# rl_energy_board.net
KiCad netlist of a schematic drawn in EAGLE
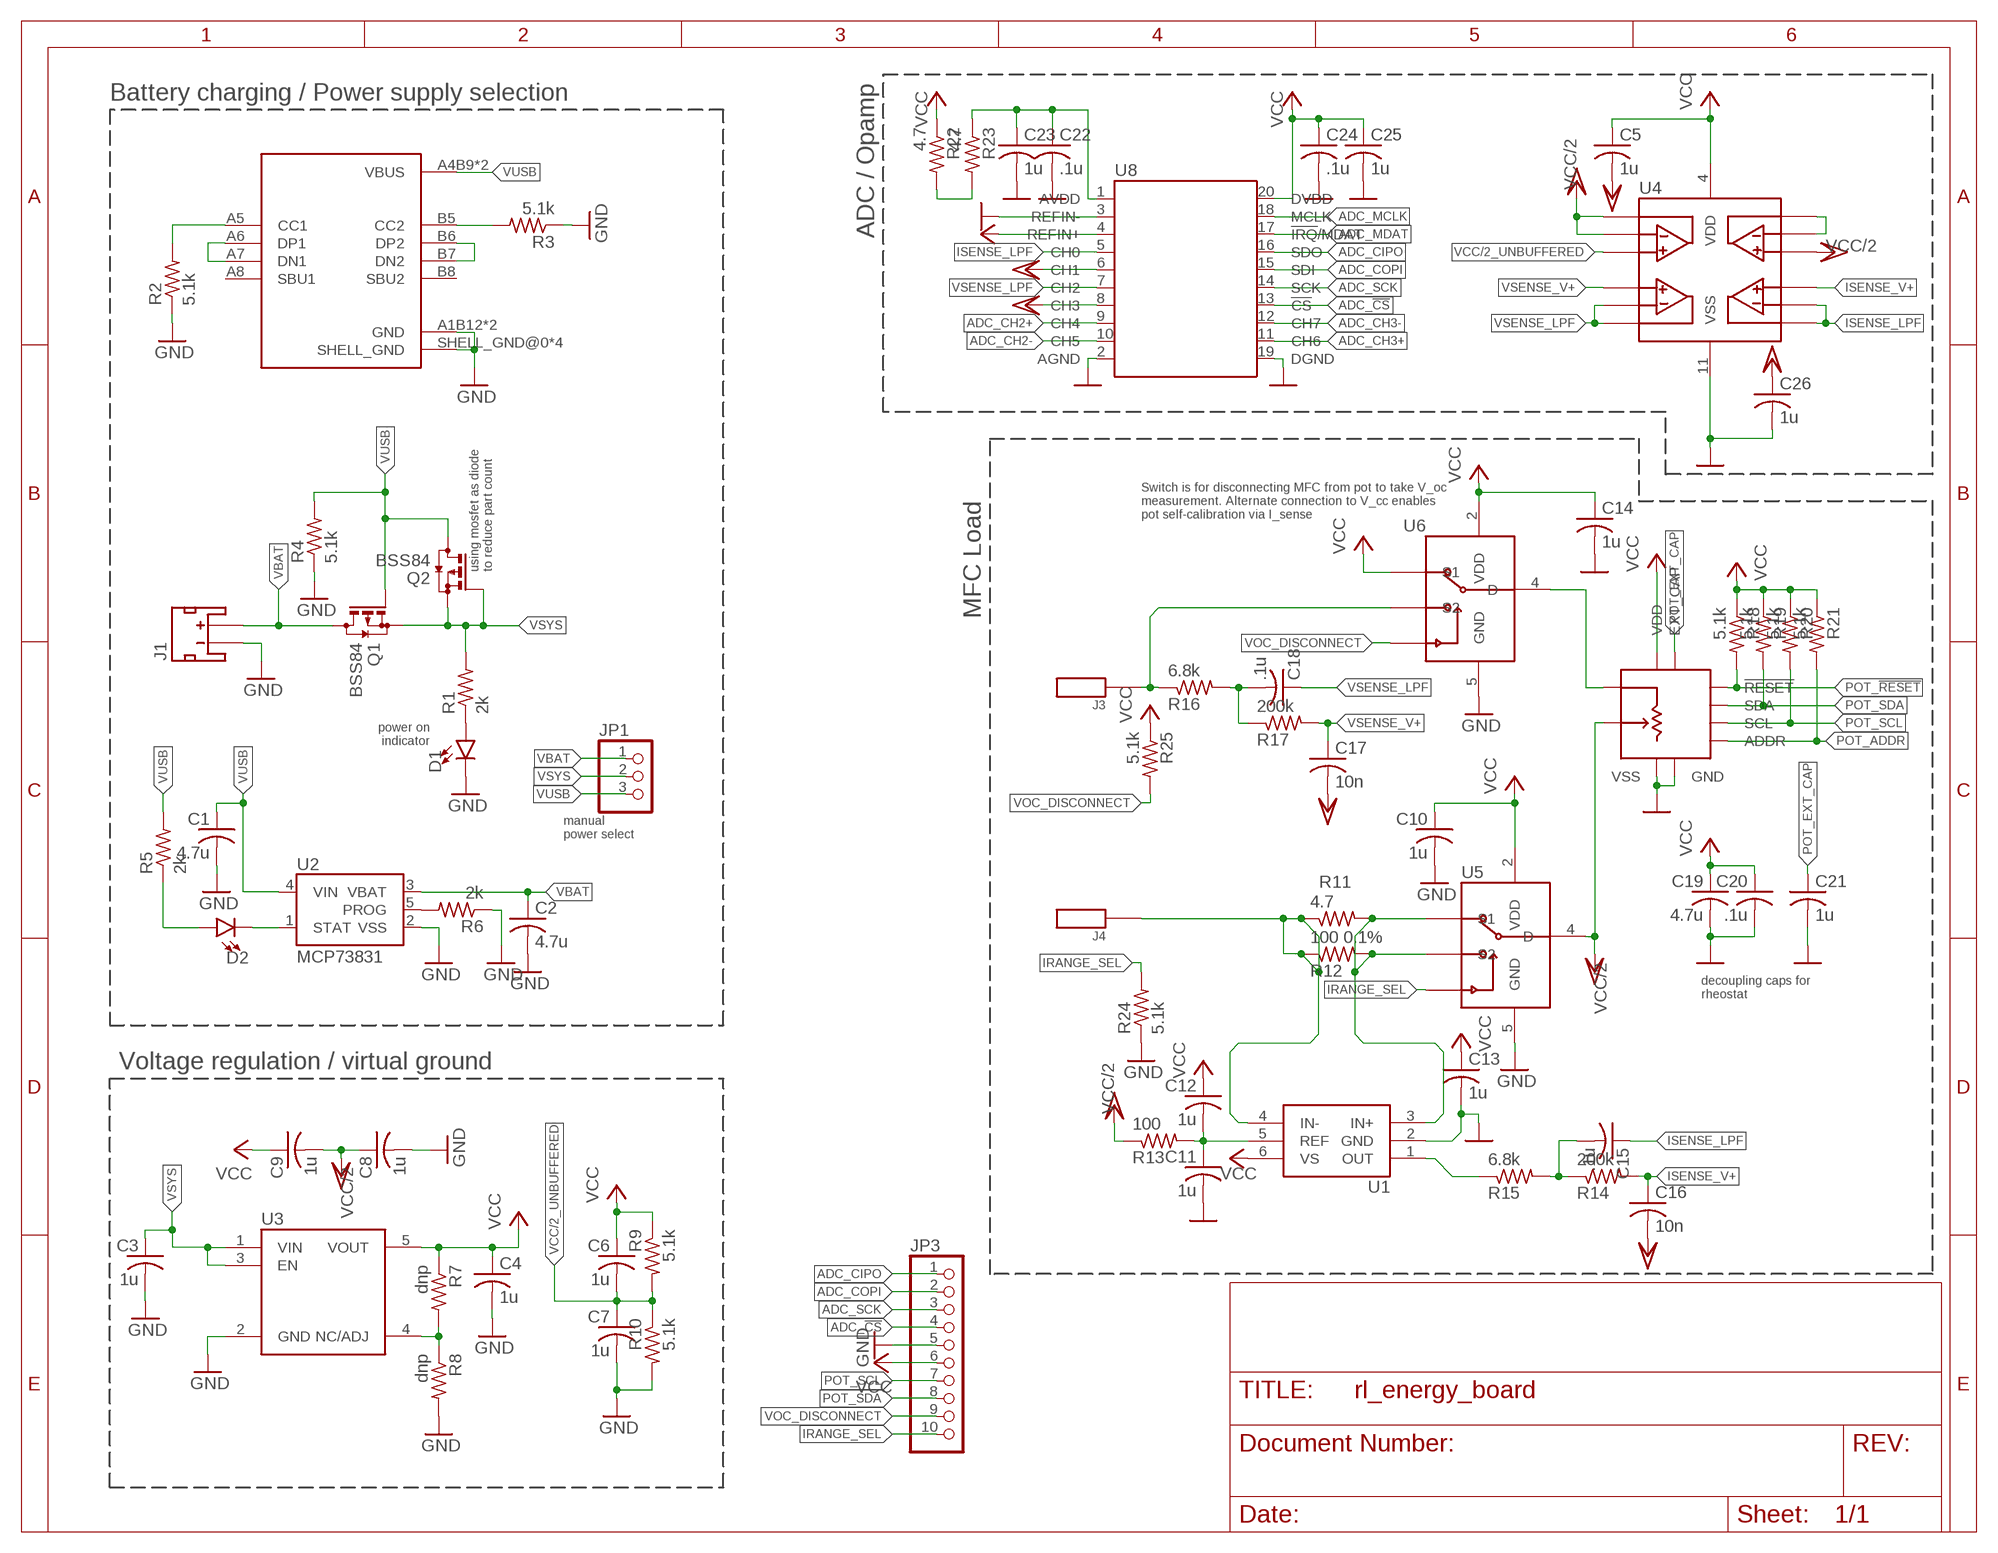
[diagram p0: schematic, sheet 1]

(export (version "E")
  (design (tool "Eeschema 10.0.6"))
  (components
    (comp (ref "C1")
      (value "4.7u")
      (footprint "eagle-import:C0603")
      (libsource (lib "eagle-import") (part "C-USC0603"))
    )
    (comp (ref "C2")
      (value "4.7u")
      (footprint "eagle-import:C0603")
      (libsource (lib "eagle-import") (part "C-USC0603"))
    )
    (comp (ref "C3")
      (value "1u")
      (footprint "eagle-import:C0603")
      (libsource (lib "eagle-import") (part "C-USC0603"))
    )
    (comp (ref "C4")
      (value "1u")
      (footprint "eagle-import:C0603")
      (libsource (lib "eagle-import") (part "C-USC0603"))
    )
    (comp (ref "C5")
      (value "1u")
      (footprint "eagle-import:C0603")
      (libsource (lib "eagle-import") (part "C-USC0603"))
    )
    (comp (ref "C6")
      (value "1u")
      (footprint "eagle-import:C0603")
      (libsource (lib "eagle-import") (part "C-USC0603"))
    )
    (comp (ref "C7")
      (value "1u")
      (footprint "eagle-import:C0603")
      (libsource (lib "eagle-import") (part "C-USC0603"))
    )
    (comp (ref "C8")
      (value "1u")
      (footprint "eagle-import:C0603")
      (libsource (lib "eagle-import") (part "C-USC0603"))
    )
    (comp (ref "C9")
      (value "1u")
      (footprint "eagle-import:C0603")
      (libsource (lib "eagle-import") (part "C-USC0603"))
    )
    (comp (ref "C10")
      (value "1u")
      (footprint "eagle-import:C0603")
      (libsource (lib "eagle-import") (part "C-USC0603"))
    )
    (comp (ref "C11")
      (value "1u")
      (footprint "eagle-import:C0603")
      (libsource (lib "eagle-import") (part "C-USC0603"))
    )
    (comp (ref "C12")
      (value "1u")
      (footprint "eagle-import:C0603")
      (libsource (lib "eagle-import") (part "C-USC0603"))
    )
    (comp (ref "C13")
      (value "1u")
      (footprint "eagle-import:C0603")
      (libsource (lib "eagle-import") (part "C-USC0603"))
    )
    (comp (ref "C14")
      (value "1u")
      (footprint "eagle-import:C0603")
      (libsource (lib "eagle-import") (part "C-USC0603"))
    )
    (comp (ref "C15")
      (value ".1u")
      (footprint "eagle-import:C0603")
      (libsource (lib "eagle-import") (part "C-USC0603"))
    )
    (comp (ref "C16")
      (value "10n")
      (footprint "eagle-import:C0603")
      (libsource (lib "eagle-import") (part "C-USC0603"))
    )
    (comp (ref "C17")
      (value "10n")
      (footprint "eagle-import:C0603")
      (libsource (lib "eagle-import") (part "C-USC0603"))
    )
    (comp (ref "C18")
      (value ".1u")
      (footprint "eagle-import:C0603")
      (libsource (lib "eagle-import") (part "C-USC0603"))
    )
    (comp (ref "C19")
      (value "4.7u")
      (footprint "eagle-import:C0603")
      (libsource (lib "eagle-import") (part "C-USC0603"))
    )
    (comp (ref "C20")
      (value ".1u")
      (footprint "eagle-import:C0603")
      (libsource (lib "eagle-import") (part "C-USC0603"))
    )
    (comp (ref "C21")
      (value "1u")
      (footprint "eagle-import:C0603")
      (libsource (lib "eagle-import") (part "C-USC0603"))
    )
    (comp (ref "C22")
      (value ".1u")
      (footprint "eagle-import:C0603")
      (libsource (lib "eagle-import") (part "C-USC0603"))
    )
    (comp (ref "C23")
      (value "1u")
      (footprint "eagle-import:C0603")
      (libsource (lib "eagle-import") (part "C-USC0603"))
    )
    (comp (ref "C24")
      (value ".1u")
      (footprint "eagle-import:C0603")
      (libsource (lib "eagle-import") (part "C-USC0603"))
    )
    (comp (ref "C25")
      (value "1u")
      (footprint "eagle-import:C0603")
      (libsource (lib "eagle-import") (part "C-USC0603"))
    )
    (comp (ref "C26")
      (value "1u")
      (footprint "eagle-import:C0603")
      (libsource (lib "eagle-import") (part "C-USC0603"))
    )
    (comp (ref "D1")
      (value "LED0603")
      (footprint "eagle-import:LED-0603")
      (fields (field (name "MFR") "Lite-On Inc."))
      (libsource (lib "eagle-import") (part "LED0603"))
    )
    (comp (ref "D2")
      (value "LED0603")
      (footprint "eagle-import:LED-0603")
      (fields (field (name "MFR") "Lite-On Inc."))
      (libsource (lib "eagle-import") (part "LED0603"))
    )
    (comp (ref "J1")
      (value "JST_2MM_MALE")
      (footprint "eagle-import:JST-2-SMD")
      (fields (field (name "MFR") "JST"))
      (libsource (lib "eagle-import") (part "JST_2MM_MALE"))
    )
    (comp (ref "J2")
      (value "USB4105")
      (footprint "eagle-import:USB4105")
      (libsource (lib "eagle-import") (part "USB4105"))
    )
    (comp (ref "J3")
      (value "CT3151V1-X")
      (footprint "eagle-import:CT3151V1")
      (libsource (lib "eagle-import") (part "CT3151V1-X"))
    )
    (comp (ref "J4")
      (value "CT3151V1-X")
      (footprint "eagle-import:CT3151V1")
      (libsource (lib "eagle-import") (part "CT3151V1-X"))
    )
    (comp (ref "JP1")
      (value "PINHD-1X3")
      (footprint "eagle-import:1X03")
      (libsource (lib "eagle-import") (part "PINHD-1X3"))
    )
    (comp (ref "JP3")
      (value "PINHD-1X10")
      (footprint "eagle-import:1X10")
      (libsource (lib "eagle-import") (part "PINHD-1X10"))
    )
    (comp (ref "Q1")
      (value "BSS84")
      (footprint "eagle-import:SOT23")
      (libsource (lib "eagle-import") (part "BSS84"))
    )
    (comp (ref "Q2")
      (value "BSS84")
      (footprint "eagle-import:SOT23")
      (libsource (lib "eagle-import") (part "BSS84"))
    )
    (comp (ref "R1")
      (value "2k")
      (footprint "eagle-import:R0603")
      (libsource (lib "eagle-import") (part "R-US_R0603"))
    )
    (comp (ref "R2")
      (value "5.1k")
      (footprint "eagle-import:R0603")
      (libsource (lib "eagle-import") (part "R-US_R0603"))
    )
    (comp (ref "R3")
      (value "5.1k")
      (footprint "eagle-import:R0603")
      (libsource (lib "eagle-import") (part "R-US_R0603"))
    )
    (comp (ref "R4")
      (value "5.1k")
      (footprint "eagle-import:R0603")
      (libsource (lib "eagle-import") (part "R-US_R0603"))
    )
    (comp (ref "R5")
      (value "2k")
      (footprint "eagle-import:R0603")
      (libsource (lib "eagle-import") (part "R-US_R0603"))
    )
    (comp (ref "R6")
      (value "2k")
      (footprint "eagle-import:R0603")
      (libsource (lib "eagle-import") (part "R-US_R0603"))
    )
    (comp (ref "R7")
      (value "dnp")
      (footprint "eagle-import:R0603")
      (libsource (lib "eagle-import") (part "R-US_R0603"))
    )
    (comp (ref "R8")
      (value "dnp")
      (footprint "eagle-import:R0603")
      (libsource (lib "eagle-import") (part "R-US_R0603"))
    )
    (comp (ref "R9")
      (value "5.1k")
      (footprint "eagle-import:R0603")
      (libsource (lib "eagle-import") (part "R-US_R0603"))
    )
    (comp (ref "R10")
      (value "5.1k")
      (footprint "eagle-import:R0603")
      (libsource (lib "eagle-import") (part "R-US_R0603"))
    )
    (comp (ref "R11")
      (value "4.7")
      (footprint "eagle-import:R0603")
      (libsource (lib "eagle-import") (part "R-US_R0603"))
    )
    (comp (ref "R12")
      (value "100 0.1%")
      (footprint "eagle-import:R0603")
      (libsource (lib "eagle-import") (part "R-US_R0603"))
    )
    (comp (ref "R13")
      (value "100")
      (footprint "eagle-import:R0603")
      (libsource (lib "eagle-import") (part "R-US_R0603"))
    )
    (comp (ref "R14")
      (value "200k")
      (footprint "eagle-import:R0603")
      (libsource (lib "eagle-import") (part "R-US_R0603"))
    )
    (comp (ref "R15")
      (value "6.8k")
      (footprint "eagle-import:R0603")
      (libsource (lib "eagle-import") (part "R-US_R0603"))
    )
    (comp (ref "R16")
      (value "6.8k")
      (footprint "eagle-import:R0603")
      (libsource (lib "eagle-import") (part "R-US_R0603"))
    )
    (comp (ref "R17")
      (value "200k")
      (footprint "eagle-import:R0603")
      (libsource (lib "eagle-import") (part "R-US_R0603"))
    )
    (comp (ref "R18")
      (value "5.1k")
      (footprint "eagle-import:R0603")
      (libsource (lib "eagle-import") (part "R-US_R0603"))
    )
    (comp (ref "R19")
      (value "5.1k")
      (footprint "eagle-import:R0603")
      (libsource (lib "eagle-import") (part "R-US_R0603"))
    )
    (comp (ref "R20")
      (value "5.1k")
      (footprint "eagle-import:R0603")
      (libsource (lib "eagle-import") (part "R-US_R0603"))
    )
    (comp (ref "R21")
      (value "5.1k")
      (footprint "eagle-import:R0603")
      (libsource (lib "eagle-import") (part "R-US_R0603"))
    )
    (comp (ref "R22")
      (value "4.7")
      (footprint "eagle-import:R0603")
      (libsource (lib "eagle-import") (part "R-US_R0603"))
    )
    (comp (ref "R23")
      (value "4.7")
      (footprint "eagle-import:R0603")
      (libsource (lib "eagle-import") (part "R-US_R0603"))
    )
    (comp (ref "R24")
      (value "5.1k")
      (footprint "eagle-import:R0603")
      (libsource (lib "eagle-import") (part "R-US_R0603"))
    )
    (comp (ref "R25")
      (value "5.1k")
      (footprint "eagle-import:R0603")
      (libsource (lib "eagle-import") (part "R-US_R0603"))
    )
    (comp (ref "U1")
      (value "INA181")
      (footprint "eagle-import:SOT95P280X145-6N")
      (libsource (lib "eagle-import") (part "INA181"))
    )
    (comp (ref "U2")
      (value "MCP73831")
      (footprint "eagle-import:SOT23-5")
      (libsource (lib "eagle-import") (part "MCP73831"))
    )
    (comp (ref "U3")
      (value "AP7366")
      (footprint "eagle-import:SOT95P285X130-5N")
      (libsource (lib "eagle-import") (part "AP7366"))
    )
    (comp (ref "U4")
      (value "MCP6074")
      (footprint "eagle-import:SOP65P640X120-14N")
      (libsource (lib "eagle-import") (part "MCP6074"))
    )
    (comp (ref "U5")
      (value "TMUX1247")
      (footprint "eagle-import:SOT65P210X110-6N")
      (libsource (lib "eagle-import") (part "TMUX1247"))
    )
    (comp (ref "U6")
      (value "TMUX1247")
      (footprint "eagle-import:SOT65P210X110-6N")
      (libsource (lib "eagle-import") (part "TMUX1247"))
    )
    (comp (ref "U7")
      (value "AD5272BRMZ-XXX")
      (footprint "eagle-import:SOP50P490X95-10N")
      (libsource (lib "eagle-import") (part "AD5272BRMZ-XXX"))
    )
    (comp (ref "U8")
      (value "MCP3564")
      (footprint "eagle-import:SOP65P640X120-20N")
      (libsource (lib "eagle-import") (part "MCP3564"))
    )
  )
  (nets
    (net (code "1") (name "/ADC_~{CS}") (class "Default")
      (node (ref "JP3") (pin "4") (pinfunction "4_4") (pintype "passive"))
      (node (ref "U8") (pin "13") (pinfunction "~{CS}_13") (pintype "bidirectional"))
    )
    (net (code "2") (name "/POT_~{RESET}") (class "Default")
      (node (ref "R18") (pin "2") (pinfunction "2_2") (pintype "passive"))
      (node (ref "U7") (pin "7") (pinfunction "~{RESET}_7") (pintype "bidirectional"))
    )
    (net (code "3") (name "ADC_CH2+") (class "Default")
      (node (ref "U8") (pin "9") (pinfunction "CH4_9") (pintype "bidirectional"))
    )
    (net (code "4") (name "ADC_CH2-") (class "Default")
      (node (ref "U8") (pin "10") (pinfunction "CH5_10") (pintype "bidirectional"))
    )
    (net (code "5") (name "ADC_CH3+") (class "Default")
      (node (ref "U8") (pin "11") (pinfunction "CH6_11") (pintype "bidirectional"))
    )
    (net (code "6") (name "ADC_CH3-") (class "Default")
      (node (ref "U8") (pin "12") (pinfunction "CH7_12") (pintype "bidirectional"))
    )
    (net (code "7") (name "ADC_CIPO") (class "Default")
      (node (ref "JP3") (pin "1") (pinfunction "1_1") (pintype "passive"))
      (node (ref "U8") (pin "16") (pinfunction "SDO_16") (pintype "bidirectional"))
    )
    (net (code "8") (name "ADC_COPI") (class "Default")
      (node (ref "JP3") (pin "2") (pinfunction "2_2") (pintype "passive"))
      (node (ref "U8") (pin "15") (pinfunction "SDI_15") (pintype "bidirectional"))
    )
    (net (code "9") (name "ADC_MCLK") (class "Default")
      (node (ref "U8") (pin "18") (pinfunction "MCLK_18") (pintype "bidirectional"))
    )
    (net (code "10") (name "ADC_MDAT") (class "Default")
      (node (ref "U8") (pin "17") (pinfunction "~{IRQ}/MDAT_17") (pintype "bidirectional"))
    )
    (net (code "11") (name "ADC_SCK") (class "Default")
      (node (ref "JP3") (pin "3") (pinfunction "3_3") (pintype "passive"))
      (node (ref "U8") (pin "14") (pinfunction "SCK_14") (pintype "bidirectional"))
    )
    (net (code "12") (name "GND") (class "Default")
      (node (ref "C1") (pin "2") (pinfunction "2_2") (pintype "passive"))
      (node (ref "C10") (pin "2") (pinfunction "2_2") (pintype "passive"))
      (node (ref "C11") (pin "2") (pinfunction "2_2") (pintype "passive"))
      (node (ref "C13") (pin "2") (pinfunction "2_2") (pintype "passive"))
      (node (ref "C14") (pin "2") (pinfunction "2_2") (pintype "passive"))
      (node (ref "C19") (pin "2") (pinfunction "2_2") (pintype "passive"))
      (node (ref "C2") (pin "2") (pinfunction "2_2") (pintype "passive"))
      (node (ref "C20") (pin "2") (pinfunction "2_2") (pintype "passive"))
      (node (ref "C21") (pin "2") (pinfunction "2_2") (pintype "passive"))
      (node (ref "C22") (pin "2") (pinfunction "2_2") (pintype "passive"))
      (node (ref "C23") (pin "2") (pinfunction "2_2") (pintype "passive"))
      (node (ref "C24") (pin "2") (pinfunction "2_2") (pintype "passive"))
      (node (ref "C25") (pin "2") (pinfunction "2_2") (pintype "passive"))
      (node (ref "C26") (pin "2") (pinfunction "2_2") (pintype "passive"))
      (node (ref "C3") (pin "2") (pinfunction "2_2") (pintype "passive"))
      (node (ref "C4") (pin "2") (pinfunction "2_2") (pintype "passive"))
      (node (ref "C7") (pin "2") (pinfunction "2_2") (pintype "passive"))
      (node (ref "C8") (pin "2") (pinfunction "2_2") (pintype "passive"))
      (node (ref "D1") (pin "C") (pinfunction "C_C") (pintype "passive"))
      (node (ref "J1") (pin "1") (pinfunction "-_1") (pintype "bidirectional"))
      (node (ref "J2") (pin "A1B12") (pinfunction "GND_A1B12") (pintype "bidirectional"))
      (node (ref "J2") (pin "B1A12") (pinfunction "GND_B1A12") (pintype "bidirectional"))
      (node (ref "J2") (pin "SHELL_GND@0") (pinfunction "SHELL_GND_SHELL_GND@0") (pintype "bidirectional"))
      (node (ref "J2") (pin "SHELL_GND@1") (pinfunction "SHELL_GND_SHELL_GND@1") (pintype "bidirectional"))
      (node (ref "J2") (pin "SHELL_GND@2") (pinfunction "SHELL_GND_SHELL_GND@2") (pintype "bidirectional"))
      (node (ref "J2") (pin "SHELL_GND@3") (pinfunction "SHELL_GND_SHELL_GND@3") (pintype "bidirectional"))
      (node (ref "JP3") (pin "5") (pinfunction "5_5") (pintype "passive"))
      (node (ref "R10") (pin "2") (pinfunction "2_2") (pintype "passive"))
      (node (ref "R2") (pin "1") (pinfunction "1_1") (pintype "passive"))
      (node (ref "R24") (pin "1") (pinfunction "1_1") (pintype "passive"))
      (node (ref "R3") (pin "1") (pinfunction "1_1") (pintype "passive"))
      (node (ref "R4") (pin "1") (pinfunction "1_1") (pintype "passive"))
      (node (ref "R6") (pin "1") (pinfunction "1_1") (pintype "passive"))
      (node (ref "R8") (pin "2") (pinfunction "2_2") (pintype "passive"))
      (node (ref "U1") (pin "2") (pinfunction "GND_2") (pintype "bidirectional"))
      (node (ref "U2") (pin "2") (pinfunction "VSS_2") (pintype "power_in"))
      (node (ref "U3") (pin "2") (pinfunction "GND_2") (pintype "bidirectional"))
      (node (ref "U4") (pin "11") (pinfunction "VSS_11") (pintype "bidirectional"))
      (node (ref "U5") (pin "5") (pinfunction "GND_5") (pintype "bidirectional"))
      (node (ref "U6") (pin "5") (pinfunction "GND_5") (pintype "bidirectional"))
      (node (ref "U7") (pin "4") (pinfunction "VSS_4") (pintype "bidirectional"))
      (node (ref "U7") (pin "6") (pinfunction "GND_6") (pintype "bidirectional"))
      (node (ref "U8") (pin "19") (pinfunction "DGND_19") (pintype "bidirectional"))
      (node (ref "U8") (pin "2") (pinfunction "AGND_2") (pintype "bidirectional"))
      (node (ref "U8") (pin "3") (pinfunction "REFIN-_3") (pintype "bidirectional"))
    )
    (net (code "13") (name "IRANGE_SEL") (class "Default")
      (node (ref "JP3") (pin "10") (pinfunction "10_10") (pintype "passive"))
      (node (ref "R24") (pin "2") (pinfunction "2_2") (pintype "passive"))
      (node (ref "U5") (pin "6") (pinfunction "SEL_6") (pintype "bidirectional"))
    )
    (net (code "14") (name "ISENSE_LPF") (class "Default")
      (node (ref "C15") (pin "1") (pinfunction "1_1") (pintype "passive"))
      (node (ref "U4") (pin "8") (pinfunction "P$8_8") (pintype "bidirectional"))
      (node (ref "U4") (pin "9") (pinfunction "P$9_9") (pintype "bidirectional"))
      (node (ref "U8") (pin "5") (pinfunction "CH0_5") (pintype "bidirectional"))
    )
    (net (code "15") (name "ISENSE_V+") (class "Default")
      (node (ref "C16") (pin "1") (pinfunction "1_1") (pintype "passive"))
      (node (ref "R14") (pin "2") (pinfunction "2_2") (pintype "passive"))
      (node (ref "U4") (pin "10") (pinfunction "P$10_10") (pintype "bidirectional"))
    )
    (net (code "16") (name "Net-(C15-Pad2)") (class "Default")
      (node (ref "C15") (pin "2") (pinfunction "2_2") (pintype "passive"))
      (node (ref "R14") (pin "1") (pinfunction "1_1") (pintype "passive"))
      (node (ref "R15") (pin "2") (pinfunction "2_2") (pintype "passive"))
    )
    (net (code "17") (name "Net-(C18-Pad2)") (class "Default")
      (node (ref "C18") (pin "2") (pinfunction "2_2") (pintype "passive"))
      (node (ref "R16") (pin "2") (pinfunction "2_2") (pintype "passive"))
      (node (ref "R17") (pin "1") (pinfunction "1_1") (pintype "passive"))
    )
    (net (code "18") (name "Net-(D1-PadA)") (class "Default")
      (node (ref "D1") (pin "A") (pinfunction "A_A") (pintype "passive"))
      (node (ref "R1") (pin "1") (pinfunction "1_1") (pintype "passive"))
    )
    (net (code "19") (name "Net-(D2-PadA)") (class "Default")
      (node (ref "D2") (pin "A") (pinfunction "A_A") (pintype "passive"))
      (node (ref "R5") (pin "1") (pinfunction "1_1") (pintype "passive"))
    )
    (net (code "20") (name "Net-(J2-CC1)") (class "Default")
      (node (ref "J2") (pin "A5") (pinfunction "CC1_A5") (pintype "bidirectional"))
      (node (ref "R2") (pin "2") (pinfunction "2_2") (pintype "passive"))
    )
    (net (code "21") (name "Net-(J2-CC2)") (class "Default")
      (node (ref "J2") (pin "B5") (pinfunction "CC2_B5") (pintype "bidirectional"))
      (node (ref "R3") (pin "2") (pinfunction "2_2") (pintype "passive"))
    )
    (net (code "22") (name "Net-(J2-DN1)") (class "Default")
      (node (ref "J2") (pin "A6") (pinfunction "DP1_A6") (pintype "bidirectional"))
      (node (ref "J2") (pin "A7") (pinfunction "DN1_A7") (pintype "bidirectional"))
    )
    (net (code "23") (name "Net-(J2-DN2)") (class "Default")
      (node (ref "J2") (pin "B6") (pinfunction "DP2_B6") (pintype "bidirectional"))
      (node (ref "J2") (pin "B7") (pinfunction "DN2_B7") (pintype "bidirectional"))
    )
    (net (code "24") (name "Net-(R22-Pad2)") (class "Default")
      (node (ref "R22") (pin "2") (pinfunction "2_2") (pintype "passive"))
      (node (ref "R23") (pin "2") (pinfunction "2_2") (pintype "passive"))
    )
    (net (code "25") (name "Net-(U1-IN+)") (class "Default")
      (node (ref "R11") (pin "2") (pinfunction "2_2") (pintype "passive"))
      (node (ref "R12") (pin "2") (pinfunction "2_2") (pintype "passive"))
      (node (ref "U1") (pin "3") (pinfunction "IN+_3") (pintype "bidirectional"))
      (node (ref "U5") (pin "1") (pinfunction "S2_1") (pintype "bidirectional"))
      (node (ref "U5") (pin "3") (pinfunction "S1_3") (pintype "bidirectional"))
    )
    (net (code "26") (name "Net-(U1-IN-)") (class "Default")
      (node (ref "J4") (pin "MNT@0") (pinfunction "P$1_MNT@0") (pintype "bidirectional"))
      (node (ref "J4") (pin "MNT@1") (pinfunction "P$1_MNT@1") (pintype "bidirectional"))
      (node (ref "J4") (pin "MNT@2") (pinfunction "P$1_MNT@2") (pintype "bidirectional"))
      (node (ref "J4") (pin "MNT@3") (pinfunction "P$1_MNT@3") (pintype "bidirectional"))
      (node (ref "R11") (pin "1") (pinfunction "1_1") (pintype "passive"))
      (node (ref "R12") (pin "1") (pinfunction "1_1") (pintype "passive"))
      (node (ref "U1") (pin "4") (pinfunction "IN-_4") (pintype "bidirectional"))
    )
    (net (code "27") (name "Net-(U1-OUT)") (class "Default")
      (node (ref "R15") (pin "1") (pinfunction "1_1") (pintype "passive"))
      (node (ref "U1") (pin "1") (pinfunction "OUT_1") (pintype "bidirectional"))
    )
    (net (code "28") (name "Net-(U1-REF)") (class "Default")
      (node (ref "C11") (pin "1") (pinfunction "1_1") (pintype "passive"))
      (node (ref "C12") (pin "2") (pinfunction "2_2") (pintype "passive"))
      (node (ref "R13") (pin "2") (pinfunction "2_2") (pintype "passive"))
      (node (ref "U1") (pin "5") (pinfunction "REF_5") (pintype "bidirectional"))
    )
    (net (code "29") (name "Net-(U2-PROG)") (class "Default")
      (node (ref "R6") (pin "2") (pinfunction "2_2") (pintype "passive"))
      (node (ref "U2") (pin "5") (pinfunction "PROG_5") (pintype "input"))
    )
    (net (code "30") (name "Net-(U2-STAT)") (class "Default")
      (node (ref "D2") (pin "C") (pinfunction "C_C") (pintype "passive"))
      (node (ref "U2") (pin "1") (pinfunction "STAT_1") (pintype "output"))
    )
    (net (code "31") (name "Net-(U3-NC{slash}ADJ)") (class "Default")
      (node (ref "R7") (pin "2") (pinfunction "2_2") (pintype "passive"))
      (node (ref "R8") (pin "1") (pinfunction "1_1") (pintype "passive"))
      (node (ref "U3") (pin "4") (pinfunction "NC/ADJ_4") (pintype "bidirectional"))
    )
    (net (code "32") (name "Net-(U4-P$13)") (class "Default")
      (node (ref "U4") (pin "13") (pinfunction "P$13_13") (pintype "bidirectional"))
      (node (ref "U4") (pin "14") (pinfunction "P$14_14") (pintype "bidirectional"))
    )
    (net (code "33") (name "Net-(U6-D)") (class "Default")
      (node (ref "U6") (pin "4") (pinfunction "D_4") (pintype "bidirectional"))
      (node (ref "U7") (pin "2") (pinfunction "A_2") (pintype "bidirectional"))
    )
    (net (code "34") (name "Net-(U6-S2)") (class "Default")
      (node (ref "J3") (pin "MNT@0") (pinfunction "P$1_MNT@0") (pintype "bidirectional"))
      (node (ref "J3") (pin "MNT@1") (pinfunction "P$1_MNT@1") (pintype "bidirectional"))
      (node (ref "J3") (pin "MNT@2") (pinfunction "P$1_MNT@2") (pintype "bidirectional"))
      (node (ref "J3") (pin "MNT@3") (pinfunction "P$1_MNT@3") (pintype "bidirectional"))
      (node (ref "R16") (pin "1") (pinfunction "1_1") (pintype "passive"))
      (node (ref "U6") (pin "1") (pinfunction "S2_1") (pintype "bidirectional"))
    )
    (net (code "35") (name "Net-(U8-AVDD)") (class "Default")
      (node (ref "C22") (pin "1") (pinfunction "1_1") (pintype "passive"))
      (node (ref "C23") (pin "1") (pinfunction "1_1") (pintype "passive"))
      (node (ref "R23") (pin "1") (pinfunction "1_1") (pintype "passive"))
      (node (ref "U8") (pin "1") (pinfunction "AVDD_1") (pintype "bidirectional"))
    )
    (net (code "36") (name "POT_ADDR") (class "Default")
      (node (ref "R21") (pin "2") (pinfunction "2_2") (pintype "passive"))
      (node (ref "U7") (pin "10") (pinfunction "ADDR_10") (pintype "bidirectional"))
    )
    (net (code "37") (name "POT_EXT_CAP") (class "Default")
      (node (ref "C21") (pin "1") (pinfunction "1_1") (pintype "passive"))
      (node (ref "U7") (pin "5") (pinfunction "EXT_CAP_5") (pintype "bidirectional"))
    )
    (net (code "38") (name "POT_SCL") (class "Default")
      (node (ref "JP3") (pin "7") (pinfunction "7_7") (pintype "passive"))
      (node (ref "R20") (pin "2") (pinfunction "2_2") (pintype "passive"))
      (node (ref "U7") (pin "9") (pinfunction "SCL_9") (pintype "bidirectional"))
    )
    (net (code "39") (name "POT_SDA") (class "Default")
      (node (ref "JP3") (pin "8") (pinfunction "8_8") (pintype "passive"))
      (node (ref "R19") (pin "2") (pinfunction "2_2") (pintype "passive"))
      (node (ref "U7") (pin "8") (pinfunction "SDA_8") (pintype "bidirectional"))
    )
    (net (code "40") (name "VBAT") (class "Default")
      (node (ref "C2") (pin "1") (pinfunction "1_1") (pintype "passive"))
      (node (ref "J1") (pin "2") (pinfunction "+_2") (pintype "bidirectional"))
      (node (ref "JP1") (pin "1") (pinfunction "1_1") (pintype "passive"))
      (node (ref "Q1") (pin "3") (pinfunction "D_3") (pintype "passive"))
      (node (ref "U2") (pin "3") (pinfunction "VBAT_3") (pintype "power_in"))
    )
    (net (code "41") (name "VCC") (class "Default")
      (node (ref "C10") (pin "1") (pinfunction "1_1") (pintype "passive"))
      (node (ref "C12") (pin "1") (pinfunction "1_1") (pintype "passive"))
      (node (ref "C13") (pin "1") (pinfunction "1_1") (pintype "passive"))
      (node (ref "C14") (pin "1") (pinfunction "1_1") (pintype "passive"))
      (node (ref "C19") (pin "1") (pinfunction "1_1") (pintype "passive"))
      (node (ref "C20") (pin "1") (pinfunction "1_1") (pintype "passive"))
      (node (ref "C24") (pin "1") (pinfunction "1_1") (pintype "passive"))
      (node (ref "C25") (pin "1") (pinfunction "1_1") (pintype "passive"))
      (node (ref "C4") (pin "1") (pinfunction "1_1") (pintype "passive"))
      (node (ref "C5") (pin "1") (pinfunction "1_1") (pintype "passive"))
      (node (ref "C6") (pin "1") (pinfunction "1_1") (pintype "passive"))
      (node (ref "C9") (pin "1") (pinfunction "1_1") (pintype "passive"))
      (node (ref "JP3") (pin "6") (pinfunction "6_6") (pintype "passive"))
      (node (ref "R18") (pin "1") (pinfunction "1_1") (pintype "passive"))
      (node (ref "R19") (pin "1") (pinfunction "1_1") (pintype "passive"))
      (node (ref "R20") (pin "1") (pinfunction "1_1") (pintype "passive"))
      (node (ref "R21") (pin "1") (pinfunction "1_1") (pintype "passive"))
      (node (ref "R22") (pin "1") (pinfunction "1_1") (pintype "passive"))
      (node (ref "R25") (pin "1") (pinfunction "1_1") (pintype "passive"))
      (node (ref "R7") (pin "1") (pinfunction "1_1") (pintype "passive"))
      (node (ref "R9") (pin "1") (pinfunction "1_1") (pintype "passive"))
      (node (ref "U1") (pin "6") (pinfunction "VS_6") (pintype "bidirectional"))
      (node (ref "U3") (pin "5") (pinfunction "VOUT_5") (pintype "bidirectional"))
      (node (ref "U4") (pin "4") (pinfunction "VDD_4") (pintype "bidirectional"))
      (node (ref "U5") (pin "2") (pinfunction "VDD_2") (pintype "bidirectional"))
      (node (ref "U6") (pin "2") (pinfunction "VDD_2") (pintype "bidirectional"))
      (node (ref "U6") (pin "3") (pinfunction "S1_3") (pintype "bidirectional"))
      (node (ref "U7") (pin "1") (pinfunction "VDD_1") (pintype "bidirectional"))
      (node (ref "U8") (pin "20") (pinfunction "DVDD_20") (pintype "bidirectional"))
      (node (ref "U8") (pin "4") (pinfunction "REFIN+_4") (pintype "bidirectional"))
    )
    (net (code "42") (name "VCC{slash}2") (class "Default")
      (node (ref "C16") (pin "2") (pinfunction "2_2") (pintype "passive"))
      (node (ref "C17") (pin "2") (pinfunction "2_2") (pintype "passive"))
      (node (ref "C26") (pin "1") (pinfunction "1_1") (pintype "passive"))
      (node (ref "C5") (pin "2") (pinfunction "2_2") (pintype "passive"))
      (node (ref "C8") (pin "1") (pinfunction "1_1") (pintype "passive"))
      (node (ref "C9") (pin "2") (pinfunction "2_2") (pintype "passive"))
      (node (ref "R13") (pin "1") (pinfunction "1_1") (pintype "passive"))
      (node (ref "U4") (pin "1") (pinfunction "P$1_1") (pintype "bidirectional"))
      (node (ref "U4") (pin "12") (pinfunction "P$12_12") (pintype "bidirectional"))
      (node (ref "U4") (pin "2") (pinfunction "P$2_2") (pintype "bidirectional"))
      (node (ref "U5") (pin "4") (pinfunction "D_4") (pintype "bidirectional"))
      (node (ref "U7") (pin "3") (pinfunction "W_3") (pintype "bidirectional"))
      (node (ref "U8") (pin "6") (pinfunction "CH1_6") (pintype "bidirectional"))
      (node (ref "U8") (pin "8") (pinfunction "CH3_8") (pintype "bidirectional"))
    )
    (net (code "43") (name "VCC{slash}2_UNBUFFERED") (class "Default")
      (node (ref "C6") (pin "2") (pinfunction "2_2") (pintype "passive"))
      (node (ref "C7") (pin "1") (pinfunction "1_1") (pintype "passive"))
      (node (ref "R10") (pin "1") (pinfunction "1_1") (pintype "passive"))
      (node (ref "R9") (pin "2") (pinfunction "2_2") (pintype "passive"))
      (node (ref "U4") (pin "3") (pinfunction "P$3_3") (pintype "bidirectional"))
    )
    (net (code "44") (name "VOC_DISCONNECT") (class "Default")
      (node (ref "JP3") (pin "9") (pinfunction "9_9") (pintype "passive"))
      (node (ref "R25") (pin "2") (pinfunction "2_2") (pintype "passive"))
      (node (ref "U6") (pin "6") (pinfunction "SEL_6") (pintype "bidirectional"))
    )
    (net (code "45") (name "VSENSE_LPF") (class "Default")
      (node (ref "C18") (pin "1") (pinfunction "1_1") (pintype "passive"))
      (node (ref "U4") (pin "6") (pinfunction "P$6_6") (pintype "bidirectional"))
      (node (ref "U4") (pin "7") (pinfunction "P$7_7") (pintype "bidirectional"))
      (node (ref "U8") (pin "7") (pinfunction "CH2_7") (pintype "bidirectional"))
    )
    (net (code "46") (name "VSENSE_V+") (class "Default")
      (node (ref "C17") (pin "1") (pinfunction "1_1") (pintype "passive"))
      (node (ref "R17") (pin "2") (pinfunction "2_2") (pintype "passive"))
      (node (ref "U4") (pin "5") (pinfunction "P$5_5") (pintype "bidirectional"))
    )
    (net (code "47") (name "VSYS") (class "Default")
      (node (ref "C3") (pin "1") (pinfunction "1_1") (pintype "passive"))
      (node (ref "JP1") (pin "2") (pinfunction "2_2") (pintype "passive"))
      (node (ref "Q1") (pin "2") (pinfunction "S_2") (pintype "passive"))
      (node (ref "Q2") (pin "1") (pinfunction "G_1") (pintype "passive"))
      (node (ref "Q2") (pin "2") (pinfunction "S_2") (pintype "passive"))
      (node (ref "R1") (pin "2") (pinfunction "2_2") (pintype "passive"))
      (node (ref "U3") (pin "1") (pinfunction "VIN_1") (pintype "bidirectional"))
      (node (ref "U3") (pin "3") (pinfunction "EN_3") (pintype "bidirectional"))
    )
    (net (code "48") (name "VUSB") (class "Default")
      (node (ref "C1") (pin "1") (pinfunction "1_1") (pintype "passive"))
      (node (ref "J2") (pin "A4B9") (pinfunction "VBUS_A4B9") (pintype "bidirectional"))
      (node (ref "J2") (pin "B4A9") (pinfunction "VBUS_B4A9") (pintype "bidirectional"))
      (node (ref "JP1") (pin "3") (pinfunction "3_3") (pintype "passive"))
      (node (ref "Q1") (pin "1") (pinfunction "G_1") (pintype "passive"))
      (node (ref "Q2") (pin "3") (pinfunction "D_3") (pintype "passive"))
      (node (ref "R4") (pin "2") (pinfunction "2_2") (pintype "passive"))
      (node (ref "R5") (pin "2") (pinfunction "2_2") (pintype "passive"))
      (node (ref "U2") (pin "4") (pinfunction "VIN_4") (pintype "power_in"))
    )
    (net (code "49") (name "unconnected-(J1-PAD1-PadNC1)") (class "Default")
      (node (ref "J1") (pin "NC1") (pinfunction "PAD1_NC1") (pintype "bidirectional"))
    )
    (net (code "50") (name "unconnected-(J1-PAD2-PadNC2)") (class "Default")
      (node (ref "J1") (pin "NC2") (pinfunction "PAD2_NC2") (pintype "bidirectional"))
    )
    (net (code "51") (name "unconnected-(J2-SBU1-PadA8)") (class "Default")
      (node (ref "J2") (pin "A8") (pinfunction "SBU1_A8") (pintype "bidirectional"))
    )
    (net (code "52") (name "unconnected-(J2-SBU2-PadB8)") (class "Default")
      (node (ref "J2") (pin "B8") (pinfunction "SBU2_B8") (pintype "bidirectional"))
    )
  )
)
